# K-Diag_small-_single.net
KiCad netlist of a schematic drawn in EAGLE
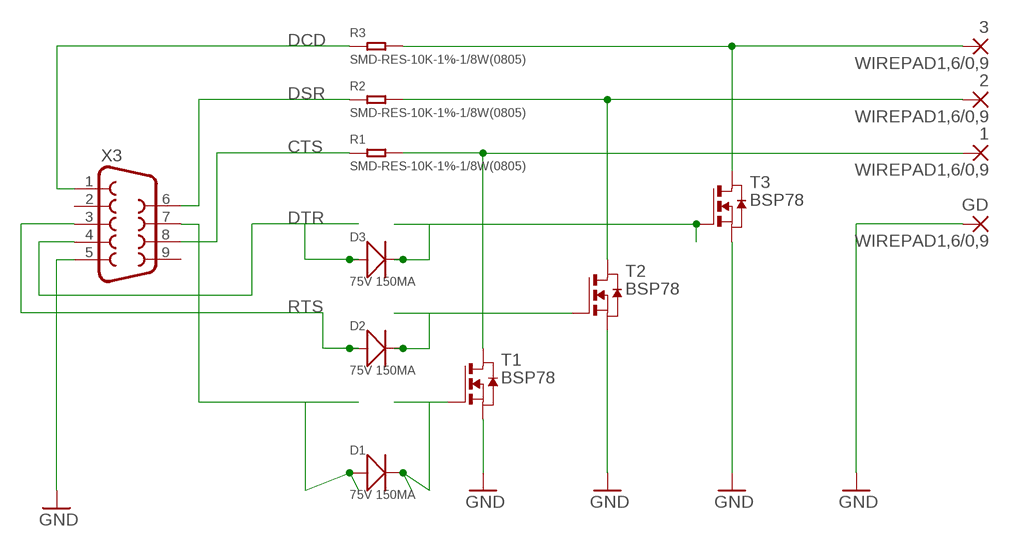
[diagram p0: schematic, sheet 1]

(export (version "E")
  (design (tool "Eeschema 10.0.6"))
  (components
    (comp (ref "1")
      (value "WIREPAD1,6/0,9")
      (footprint "eagle-import:1,6_0,9")
      (libsource (lib "eagle-import") (part "WIREPAD1,6/0,9"))
    )
    (comp (ref "2")
      (value "WIREPAD1,6/0,9")
      (footprint "eagle-import:1,6_0,9")
      (libsource (lib "eagle-import") (part "WIREPAD1,6/0,9"))
    )
    (comp (ref "3")
      (value "WIREPAD1,6/0,9")
      (footprint "eagle-import:1,6_0,9")
      (libsource (lib "eagle-import") (part "WIREPAD1,6/0,9"))
    )
    (comp (ref "D1")
      (value "75V 150MA")
      (footprint "eagle-import:LED-1206")
      (fields (field (name "MPN") "CD1206-S01575"))
      (libsource (lib "eagle-import") (part "SMD-DIODE-SWITCHING-75V-150MA(D1206)"))
    )
    (comp (ref "D2")
      (value "75V 150MA")
      (footprint "eagle-import:LED-1206")
      (fields (field (name "MPN") "CD1206-S01575"))
      (libsource (lib "eagle-import") (part "SMD-DIODE-SWITCHING-75V-150MA(D1206)"))
    )
    (comp (ref "D3")
      (value "75V 150MA")
      (footprint "eagle-import:LED-1206")
      (fields (field (name "MPN") "CD1206-S01575"))
      (libsource (lib "eagle-import") (part "SMD-DIODE-SWITCHING-75V-150MA(D1206)"))
    )
    (comp (ref "GD")
      (value "WIREPAD1,6/0,9")
      (footprint "eagle-import:1,6_0,9")
      (libsource (lib "eagle-import") (part "WIREPAD1,6/0,9"))
    )
    (comp (ref "R1")
      (value "SMD-RES-10K-1%-1/8W(0805)")
      (footprint "eagle-import:R0805")
      (fields (field (name "MPN") "RC0805FR-0710KL"))
      (libsource (lib "eagle-import") (part "SMD-RES-10K-1%-1/8W(0805)"))
    )
    (comp (ref "R2")
      (value "SMD-RES-10K-1%-1/8W(0805)")
      (footprint "eagle-import:R0805")
      (fields (field (name "MPN") "RC0805FR-0710KL"))
      (libsource (lib "eagle-import") (part "SMD-RES-10K-1%-1/8W(0805)"))
    )
    (comp (ref "R3")
      (value "SMD-RES-10K-1%-1/8W(0805)")
      (footprint "eagle-import:R0805")
      (fields (field (name "MPN") "RC0805FR-0710KL"))
      (libsource (lib "eagle-import") (part "SMD-RES-10K-1%-1/8W(0805)"))
    )
    (comp (ref "T1")
      (value "BSP78")
      (footprint "eagle-import:SOT223")
      (libsource (lib "eagle-import") (part "NMOSSOT223"))
    )
    (comp (ref "T2")
      (value "BSP78")
      (footprint "eagle-import:SOT223")
      (libsource (lib "eagle-import") (part "NMOSSOT223"))
    )
    (comp (ref "T3")
      (value "BSP78")
      (footprint "eagle-import:SOT223")
      (libsource (lib "eagle-import") (part "NMOSSOT223"))
    )
    (comp (ref "X3")
      (value "F09D")
      (footprint "eagle-import:F09D")
      (libsource (lib "eagle-import") (part "F09D"))
    )
  )
  (nets
    (net (code "1") (name "/CTS") (class "Default")
      (node (ref "R1") (pin "1") (pinfunction "1_1") (pintype "passive"))
      (node (ref "X3") (pin "8") (pinfunction "8_8") (pintype "passive"))
    )
    (net (code "2") (name "/DCD") (class "Default")
      (node (ref "R3") (pin "1") (pinfunction "1_1") (pintype "passive"))
      (node (ref "X3") (pin "1") (pinfunction "1_1") (pintype "passive"))
    )
    (net (code "3") (name "/DSR") (class "Default")
      (node (ref "R2") (pin "1") (pinfunction "1_1") (pintype "passive"))
      (node (ref "X3") (pin "6") (pinfunction "6_6") (pintype "passive"))
    )
    (net (code "4") (name "/DTR") (class "Default")
      (node (ref "D3") (pin "+") (pinfunction "+_+") (pintype "passive"))
      (node (ref "X3") (pin "4") (pinfunction "4_4") (pintype "passive"))
    )
    (net (code "5") (name "/RTS") (class "Default")
      (node (ref "D2") (pin "+") (pinfunction "+_+") (pintype "passive"))
      (node (ref "X3") (pin "3") (pinfunction "3_3") (pintype "passive"))
    )
    (net (code "6") (name "GND") (class "Default")
      (node (ref "GD") (pin "1") (pinfunction "P_1") (pintype "passive"))
      (node (ref "T1") (pin "3") (pinfunction "S_3") (pintype "passive"))
      (node (ref "T2") (pin "3") (pinfunction "S_3") (pintype "passive"))
      (node (ref "T3") (pin "3") (pinfunction "S_3") (pintype "passive"))
      (node (ref "X3") (pin "5") (pinfunction "5_5") (pintype "passive"))
    )
    (net (code "7") (name "Net-(1-P)") (class "Default")
      (node (ref "1") (pin "1") (pinfunction "P_1") (pintype "passive"))
      (node (ref "R1") (pin "2") (pinfunction "2_2") (pintype "passive"))
      (node (ref "T1") (pin "2") (pinfunction "D_2") (pintype "passive"))
      (node (ref "T1") (pin "4") (pinfunction "D_4") (pintype "passive"))
    )
    (net (code "8") (name "Net-(2-P)") (class "Default")
      (node (ref "2") (pin "1") (pinfunction "P_1") (pintype "passive"))
      (node (ref "R2") (pin "2") (pinfunction "2_2") (pintype "passive"))
      (node (ref "T2") (pin "2") (pinfunction "D_2") (pintype "passive"))
      (node (ref "T2") (pin "4") (pinfunction "D_4") (pintype "passive"))
    )
    (net (code "9") (name "Net-(3-P)") (class "Default")
      (node (ref "3") (pin "1") (pinfunction "P_1") (pintype "passive"))
      (node (ref "R3") (pin "2") (pinfunction "2_2") (pintype "passive"))
      (node (ref "T3") (pin "2") (pinfunction "D_2") (pintype "passive"))
      (node (ref "T3") (pin "4") (pinfunction "D_4") (pintype "passive"))
    )
    (net (code "10") (name "Net-(D1-Pad+)") (class "Default")
      (node (ref "D1") (pin "+") (pinfunction "+_+") (pintype "passive"))
      (node (ref "X3") (pin "7") (pinfunction "7_7") (pintype "passive"))
    )
    (net (code "11") (name "Net-(T1-G)") (class "Default")
      (node (ref "D1") (pin "-") (pinfunction "-_-") (pintype "passive"))
      (node (ref "T1") (pin "1") (pinfunction "G_1") (pintype "passive"))
    )
    (net (code "12") (name "Net-(T2-G)") (class "Default")
      (node (ref "D2") (pin "-") (pinfunction "-_-") (pintype "passive"))
      (node (ref "T2") (pin "1") (pinfunction "G_1") (pintype "passive"))
    )
    (net (code "13") (name "Net-(T3-G)") (class "Default")
      (node (ref "D3") (pin "-") (pinfunction "-_-") (pintype "passive"))
      (node (ref "T3") (pin "1") (pinfunction "G_1") (pintype "passive"))
    )
    (net (code "14") (name "unconnected-(X3-Pad2)") (class "Default")
      (node (ref "X3") (pin "2") (pinfunction "2_2") (pintype "passive"))
    )
    (net (code "15") (name "unconnected-(X3-Pad9)") (class "Default")
      (node (ref "X3") (pin "9") (pinfunction "9_9") (pintype "passive"))
    )
  )
)
